# AlcoholDetectieV2.net
KiCad netlist of a schematic drawn in Altium Designer
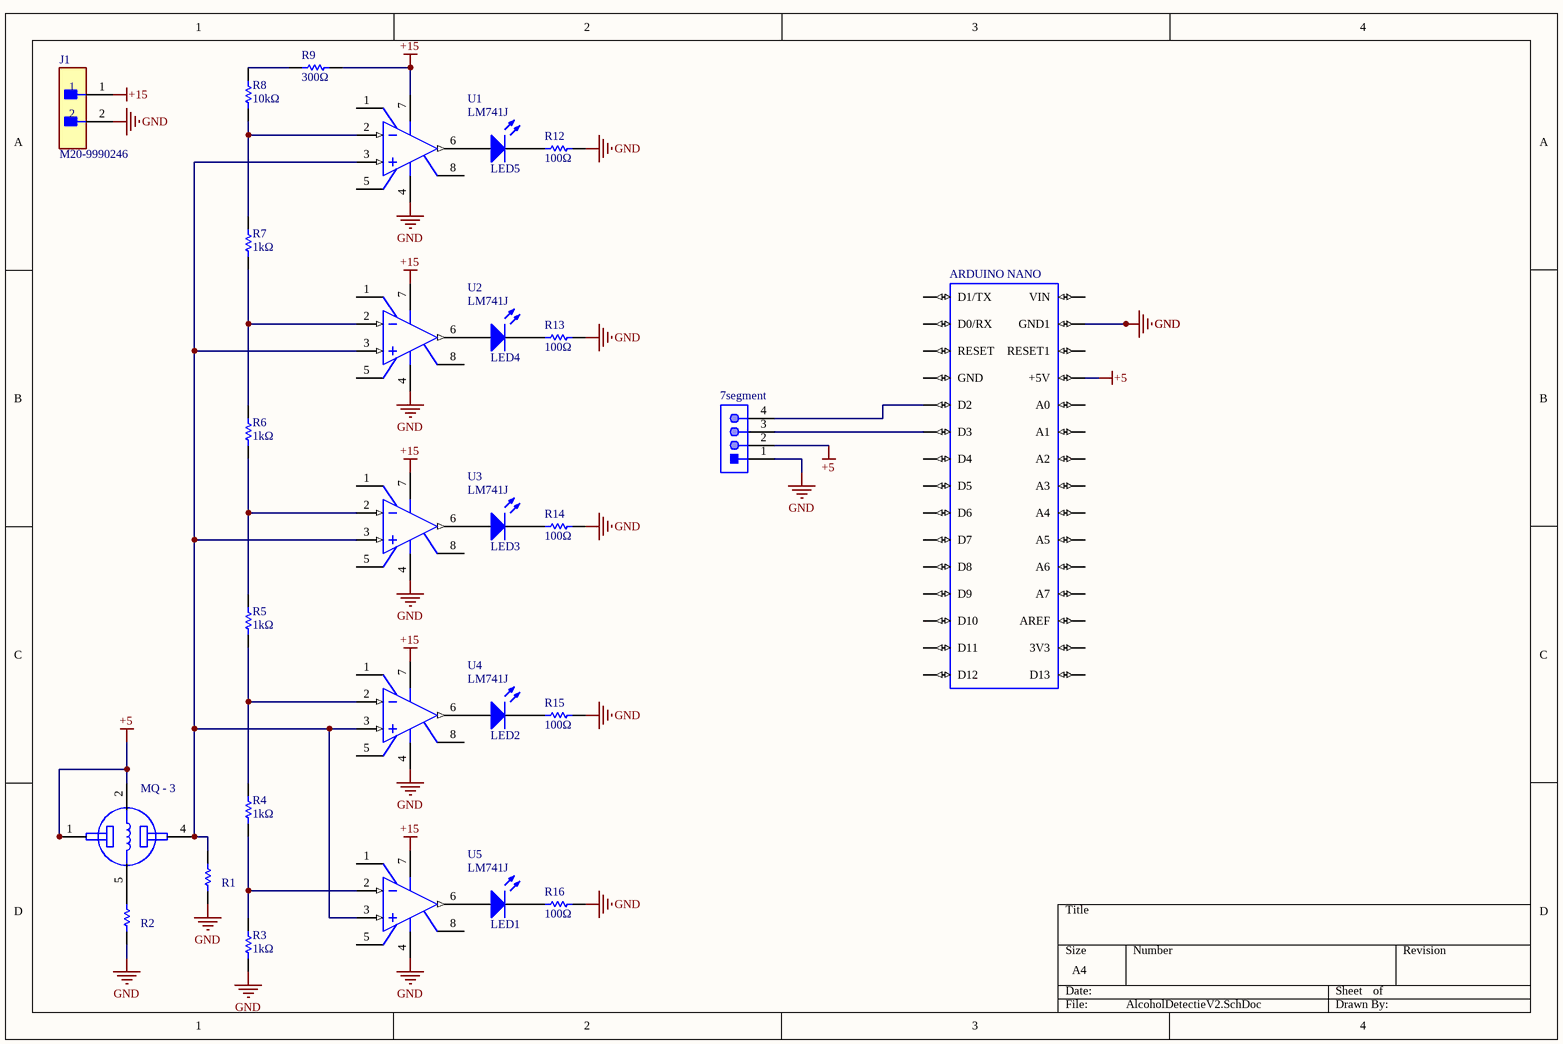
[diagram p0: AlcoholDetectieV2.SchDoc]

(export (version "E")
  (design (tool "Eeschema 10.0.6"))
  (components
    (comp (ref "7segment")
      (value "61300411121")
      (footprint "61300411121")
      (description "THT Vertical Pin Header WR-PHD, Pitch 2.54 mm, Single Row, 4 pins")
      (fields (field (name "MANUFACTURER") "Wurth Elektronik") (field (name "PUBLISHER") "WurthElektronik"))
      (libsource (lib "Altium Content Vault") (part "WE-CN-1P-M-R4"))
    )
    (comp (ref "ARDUINO NANO")
      (value "ARDUINONANO")
      (footprint "PDIP-32")
      (description "Arduino; 20MHz; 3.3Ã·5VDC; Flash: 32kB; SRAM: 2kB; ATMEGA328,FT232R")
      (fields (field (name "MF") "Arduino"))
      (libsource (lib "ARDUINONANO") (part "ARDUINONANO"))
    )
    (comp (ref "GROEN")
      (value "LED1")
      (footprint "LED-1")
      (description "Typical RED GaAs LED")
      (fields (field (name "PUBLISHER") "Altium Limited"))
      (libsource (lib "Miscellaneous Devices") (part "LED1"))
    )
    (comp (ref "J1")
      (value "M20-9990246")
      (footprint "FP-M20-9990246-MFG")
      (description "CONN HEADER VERT 2POS 2.54MM")
      (fields
        (field (name "OCTOPART") "https://octopart.com/m20-9990246-harwin-2590635")
        (field (name "MANUFACTURER") "Harwin")
      )
      (libsource (lib "Altium Content Vault") (part "3bc925449376181038e59eaffc5286c"))
    )
    (comp (ref "MQ - 3")
      (value "SEN-08880")
      (footprint "XDCR_SEN-08880")
      (description "Alcohol _C2H6O_ Sensor 0 V ~ 3.3 V")
      (fields (field (name "MF") "SparkFun Electronics"))
      (libsource (lib "SEN-08880") (part "SEN-08880"))
    )
    (comp (ref "ORANJE_1")
      (value "LED2")
      (footprint "LED-1")
      (description "Typical RED GaAs LED")
      (fields (field (name "PUBLISHER") "Altium Limited"))
      (libsource (lib "Miscellaneous Devices") (part "LED1"))
    )
    (comp (ref "ORANJE_2")
      (value "LED3")
      (footprint "LED-1")
      (description "Typical RED GaAs LED")
      (fields (field (name "PUBLISHER") "Altium Limited"))
      (libsource (lib "Miscellaneous Devices") (part "LED1"))
    )
    (comp (ref "R1")
      (value "1k Ω")
      (footprint "RESC2013X50X30LL20T20")
      (fields (field (name "MANUFACTURER") "Vishay Dale") (field (name "PART NUMBER") "CRCW08050000Z0EA"))
      (libsource (lib "Altium Content Vault") (part "RES"))
    )
    (comp (ref "R2")
      (value "5,1 Ω")
      (footprint "RESC2013X50X30LL20T20")
      (fields (field (name "MANUFACTURER") "Vishay Dale") (field (name "PART NUMBER") "CRCW08050000Z0EA"))
      (libsource (lib "Altium Content Vault") (part "RES"))
    )
    (comp (ref "R3")
      (value "1kΩ")
      (footprint "RESC2013X50X30LL20T20")
      (fields (field (name "MANUFACTURER") "Vishay Dale") (field (name "PART NUMBER") "CRCW08050000Z0EA"))
      (libsource (lib "Altium Content Vault") (part "RES"))
    )
    (comp (ref "R4")
      (value "1kΩ")
      (footprint "RESC2013X50X30LL20T20")
      (fields (field (name "MANUFACTURER") "Vishay Dale") (field (name "PART NUMBER") "CRCW08050000Z0EA"))
      (libsource (lib "Altium Content Vault") (part "RES"))
    )
    (comp (ref "R5")
      (value "1kΩ")
      (footprint "RESC2013X50X30LL20T20")
      (fields (field (name "MANUFACTURER") "Vishay Dale") (field (name "PART NUMBER") "CRCW08050000Z0EA"))
      (libsource (lib "Altium Content Vault") (part "RES"))
    )
    (comp (ref "R6")
      (value "1kΩ")
      (footprint "RESC2013X50X30LL20T20")
      (fields (field (name "MANUFACTURER") "Vishay Dale") (field (name "PART NUMBER") "CRCW08050000Z0EA"))
      (libsource (lib "Altium Content Vault") (part "RES"))
    )
    (comp (ref "R7")
      (value "1kΩ")
      (footprint "RESC2013X50X30LL20T20")
      (fields (field (name "MANUFACTURER") "Vishay Dale") (field (name "PART NUMBER") "CRCW08050000Z0EA"))
      (libsource (lib "Altium Content Vault") (part "RES"))
    )
    (comp (ref "R8")
      (value "10kΩ")
      (footprint "RESC2013X50X30LL20T20")
      (fields (field (name "MANUFACTURER") "Vishay Dale") (field (name "PART NUMBER") "CRCW08050000Z0EA"))
      (libsource (lib "Altium Content Vault") (part "RES"))
    )
    (comp (ref "R9")
      (value "300Ω")
      (footprint "RESC2013X50X30LL20T20")
      (fields (field (name "MANUFACTURER") "Vishay Dale") (field (name "PART NUMBER") "CRCW08050000Z0EA"))
      (libsource (lib "Altium Content Vault") (part "RES"))
    )
    (comp (ref "R12")
      (value "100Ω")
      (footprint "RESC2013X50X30LL20T20")
      (fields (field (name "MANUFACTURER") "Vishay Dale") (field (name "PART NUMBER") "CRCW08050000Z0EA"))
      (libsource (lib "Altium Content Vault") (part "RES"))
    )
    (comp (ref "R13")
      (value "100Ω")
      (footprint "RESC2013X50X30LL20T20")
      (fields (field (name "MANUFACTURER") "Vishay Dale") (field (name "PART NUMBER") "CRCW08050000Z0EA"))
      (libsource (lib "Altium Content Vault") (part "RES"))
    )
    (comp (ref "R14")
      (value "100Ω")
      (footprint "RESC2013X50X30LL20T20")
      (fields (field (name "MANUFACTURER") "Vishay Dale") (field (name "PART NUMBER") "CRCW08050000Z0EA"))
      (libsource (lib "Altium Content Vault") (part "RES"))
    )
    (comp (ref "R15")
      (value "100Ω")
      (footprint "RESC2013X50X30LL20T20")
      (fields (field (name "MANUFACTURER") "Vishay Dale") (field (name "PART NUMBER") "CRCW08050000Z0EA"))
      (libsource (lib "Altium Content Vault") (part "RES"))
    )
    (comp (ref "R16")
      (value "100Ω")
      (footprint "RESC2013X50X30LL20T20")
      (fields (field (name "MANUFACTURER") "Vishay Dale") (field (name "PART NUMBER") "CRCW08050000Z0EA"))
      (libsource (lib "Altium Content Vault") (part "RES"))
    )
    (comp (ref "ROOD_1")
      (value "LED4")
      (footprint "LED-1")
      (description "Typical RED GaAs LED")
      (fields (field (name "PUBLISHER") "Altium Limited"))
      (libsource (lib "Miscellaneous Devices") (part "LED1"))
    )
    (comp (ref "ROOD_2")
      (value "LED5")
      (footprint "LED-1")
      (description "Typical RED GaAs LED")
      (fields (field (name "PUBLISHER") "Altium Limited"))
      (libsource (lib "Miscellaneous Devices") (part "LED1"))
    )
    (comp (ref "U1")
      (value "LM741J")
      (footprint "NAB0008A")
      (description "Operational Amplifier, 8-pin CerDIP")
      (fields (field (name "MANUFACTURER") "Texas Instruments"))
      (libsource (lib "Altium Content Vault") (part "AMP-OPA-LM741-8"))
    )
    (comp (ref "U2")
      (value "LM741J")
      (footprint "NAB0008A")
      (description "Operational Amplifier, 8-pin CerDIP")
      (fields (field (name "MANUFACTURER") "Texas Instruments"))
      (libsource (lib "Altium Content Vault") (part "AMP-OPA-LM741-8"))
    )
    (comp (ref "U3")
      (value "LM741J")
      (footprint "NAB0008A")
      (description "Operational Amplifier, 8-pin CerDIP")
      (fields (field (name "MANUFACTURER") "Texas Instruments"))
      (libsource (lib "Altium Content Vault") (part "AMP-OPA-LM741-8"))
    )
    (comp (ref "U4")
      (value "LM741J")
      (footprint "NAB0008A")
      (description "Operational Amplifier, 8-pin CerDIP")
      (fields (field (name "MANUFACTURER") "Texas Instruments"))
      (libsource (lib "Altium Content Vault") (part "AMP-OPA-LM741-8"))
    )
    (comp (ref "U5")
      (value "LM741J")
      (footprint "NAB0008A")
      (description "Operational Amplifier, 8-pin CerDIP")
      (fields (field (name "MANUFACTURER") "Texas Instruments"))
      (libsource (lib "Altium Content Vault") (part "AMP-OPA-LM741-8"))
    )
  )
  (nets
    (net (code "1") (name "+5") (class "Default")
      (node (ref "7segment") (pin "2") (pinfunction "2_2") (pintype "passive"))
      (node (ref "ARDUINO NANO") (pin "+5V") (pinfunction "+5V_+5V") (pintype "bidirectional"))
      (node (ref "MQ - 3") (pin "1") (pinfunction "A_1") (pintype "passive"))
      (node (ref "MQ - 3") (pin "2") (pinfunction "H1_2") (pintype "passive"))
      (node (ref "MQ - 3") (pin "3") (pinfunction "A_3") (pintype "passive"))
    )
    (net (code "2") (name "+15") (class "Default")
      (node (ref "J1") (pin "1") (pinfunction "1_1") (pintype "passive"))
      (node (ref "R9") (pin "1") (pinfunction "1_1") (pintype "passive"))
      (node (ref "U1") (pin "7") (pinfunction "V+_7") (pintype "power_in"))
      (node (ref "U2") (pin "7") (pinfunction "V+_7") (pintype "power_in"))
      (node (ref "U3") (pin "7") (pinfunction "V+_7") (pintype "power_in"))
      (node (ref "U4") (pin "7") (pinfunction "V+_7") (pintype "power_in"))
      (node (ref "U5") (pin "7") (pinfunction "V+_7") (pintype "power_in"))
    )
    (net (code "3") (name "GND") (class "Default")
      (node (ref "7segment") (pin "1") (pinfunction "1_1") (pintype "passive"))
      (node (ref "ARDUINO NANO") (pin "GND1") (pinfunction "GND1_GND1") (pintype "bidirectional"))
      (node (ref "J1") (pin "2") (pinfunction "2_2") (pintype "passive"))
      (node (ref "R1") (pin "1") (pinfunction "1_1") (pintype "passive"))
      (node (ref "R12") (pin "1") (pinfunction "1_1") (pintype "passive"))
      (node (ref "R13") (pin "1") (pinfunction "1_1") (pintype "passive"))
      (node (ref "R14") (pin "1") (pinfunction "1_1") (pintype "passive"))
      (node (ref "R15") (pin "1") (pinfunction "1_1") (pintype "passive"))
      (node (ref "R16") (pin "1") (pinfunction "1_1") (pintype "passive"))
      (node (ref "R2") (pin "1") (pinfunction "1_1") (pintype "passive"))
      (node (ref "R3") (pin "1") (pinfunction "1_1") (pintype "passive"))
      (node (ref "U1") (pin "4") (pinfunction "V-_4") (pintype "power_in"))
      (node (ref "U2") (pin "4") (pinfunction "V-_4") (pintype "power_in"))
      (node (ref "U3") (pin "4") (pinfunction "V-_4") (pintype "power_in"))
      (node (ref "U4") (pin "4") (pinfunction "V-_4") (pintype "power_in"))
      (node (ref "U5") (pin "4") (pinfunction "V-_4") (pintype "power_in"))
    )
    (net (code "4") (name "Net-(7segment-Pad3)") (class "Default")
      (node (ref "7segment") (pin "3") (pinfunction "3_3") (pintype "passive"))
      (node (ref "ARDUINO NANO") (pin "D3") (pinfunction "D3_D3") (pintype "bidirectional"))
    )
    (net (code "5") (name "Net-(7segment-Pad4)") (class "Default")
      (node (ref "7segment") (pin "4") (pinfunction "4_4") (pintype "passive"))
      (node (ref "ARDUINO NANO") (pin "D2") (pinfunction "D2_D2") (pintype "bidirectional"))
    )
    (net (code "6") (name "Net-(GROEN-A)") (class "Default")
      (node (ref "GROEN") (pin "1") (pinfunction "A_1") (pintype "passive"))
      (node (ref "U5") (pin "6") (pinfunction "OUT_6") (pintype "output"))
    )
    (net (code "7") (name "Net-(GROEN-K)") (class "Default")
      (node (ref "GROEN") (pin "2") (pinfunction "K_2") (pintype "passive"))
      (node (ref "R16") (pin "2") (pinfunction "2_2") (pintype "passive"))
    )
    (net (code "8") (name "Net-(MQ - 3-H2)") (class "Default")
      (node (ref "MQ - 3") (pin "5") (pinfunction "H2_5") (pintype "passive"))
      (node (ref "R2") (pin "2") (pinfunction "2_2") (pintype "passive"))
    )
    (net (code "9") (name "Net-(ORANJE_1-A)") (class "Default")
      (node (ref "ORANJE_1") (pin "1") (pinfunction "A_1") (pintype "passive"))
      (node (ref "U4") (pin "6") (pinfunction "OUT_6") (pintype "output"))
    )
    (net (code "10") (name "Net-(ORANJE_1-K)") (class "Default")
      (node (ref "ORANJE_1") (pin "2") (pinfunction "K_2") (pintype "passive"))
      (node (ref "R15") (pin "2") (pinfunction "2_2") (pintype "passive"))
    )
    (net (code "11") (name "Net-(ORANJE_2-A)") (class "Default")
      (node (ref "ORANJE_2") (pin "1") (pinfunction "A_1") (pintype "passive"))
      (node (ref "U3") (pin "6") (pinfunction "OUT_6") (pintype "output"))
    )
    (net (code "12") (name "Net-(ORANJE_2-K)") (class "Default")
      (node (ref "ORANJE_2") (pin "2") (pinfunction "K_2") (pintype "passive"))
      (node (ref "R14") (pin "2") (pinfunction "2_2") (pintype "passive"))
    )
    (net (code "13") (name "Net-(R8-Pad2)") (class "Default")
      (node (ref "R8") (pin "2") (pinfunction "2_2") (pintype "passive"))
      (node (ref "R9") (pin "2") (pinfunction "2_2") (pintype "passive"))
    )
    (net (code "14") (name "Net-(ROOD_1-A)") (class "Default")
      (node (ref "ROOD_1") (pin "1") (pinfunction "A_1") (pintype "passive"))
      (node (ref "U2") (pin "6") (pinfunction "OUT_6") (pintype "output"))
    )
    (net (code "15") (name "Net-(ROOD_1-K)") (class "Default")
      (node (ref "R13") (pin "2") (pinfunction "2_2") (pintype "passive"))
      (node (ref "ROOD_1") (pin "2") (pinfunction "K_2") (pintype "passive"))
    )
    (net (code "16") (name "Net-(ROOD_2-A)") (class "Default")
      (node (ref "ROOD_2") (pin "1") (pinfunction "A_1") (pintype "passive"))
      (node (ref "U1") (pin "6") (pinfunction "OUT_6") (pintype "output"))
    )
    (net (code "17") (name "Net-(ROOD_2-K)") (class "Default")
      (node (ref "R12") (pin "2") (pinfunction "2_2") (pintype "passive"))
      (node (ref "ROOD_2") (pin "2") (pinfunction "K_2") (pintype "passive"))
    )
    (net (code "18") (name "Net-(U1-IN+)") (class "Default")
      (node (ref "MQ - 3") (pin "4") (pinfunction "B_4") (pintype "passive"))
      (node (ref "MQ - 3") (pin "6") (pinfunction "B_6") (pintype "passive"))
      (node (ref "R1") (pin "2") (pinfunction "2_2") (pintype "passive"))
      (node (ref "U1") (pin "3") (pinfunction "IN+_3") (pintype "input"))
      (node (ref "U2") (pin "3") (pinfunction "IN+_3") (pintype "input"))
      (node (ref "U3") (pin "3") (pinfunction "IN+_3") (pintype "input"))
      (node (ref "U4") (pin "3") (pinfunction "IN+_3") (pintype "input"))
      (node (ref "U5") (pin "3") (pinfunction "IN+_3") (pintype "input"))
    )
    (net (code "19") (name "Net-(U1-IN-)") (class "Default")
      (node (ref "R7") (pin "2") (pinfunction "2_2") (pintype "passive"))
      (node (ref "R8") (pin "1") (pinfunction "1_1") (pintype "passive"))
      (node (ref "U1") (pin "2") (pinfunction "IN-_2") (pintype "input"))
    )
    (net (code "20") (name "Net-(U2-IN-)") (class "Default")
      (node (ref "R6") (pin "2") (pinfunction "2_2") (pintype "passive"))
      (node (ref "R7") (pin "1") (pinfunction "1_1") (pintype "passive"))
      (node (ref "U2") (pin "2") (pinfunction "IN-_2") (pintype "input"))
    )
    (net (code "21") (name "Net-(U3-IN-)") (class "Default")
      (node (ref "R5") (pin "2") (pinfunction "2_2") (pintype "passive"))
      (node (ref "R6") (pin "1") (pinfunction "1_1") (pintype "passive"))
      (node (ref "U3") (pin "2") (pinfunction "IN-_2") (pintype "input"))
    )
    (net (code "22") (name "Net-(U4-IN-)") (class "Default")
      (node (ref "R4") (pin "2") (pinfunction "2_2") (pintype "passive"))
      (node (ref "R5") (pin "1") (pinfunction "1_1") (pintype "passive"))
      (node (ref "U4") (pin "2") (pinfunction "IN-_2") (pintype "input"))
    )
    (net (code "23") (name "Net-(U5-IN-)") (class "Default")
      (node (ref "R3") (pin "2") (pinfunction "2_2") (pintype "passive"))
      (node (ref "R4") (pin "1") (pinfunction "1_1") (pintype "passive"))
      (node (ref "U5") (pin "2") (pinfunction "IN-_2") (pintype "input"))
    )
    (net (code "24") (name "unconnected-(ARDUINO NANO-Pad3V3)") (class "Default")
      (node (ref "ARDUINO NANO") (pin "3V3") (pinfunction "3V3_3V3") (pintype "bidirectional"))
    )
    (net (code "25") (name "unconnected-(ARDUINO NANO-PadA0)") (class "Default")
      (node (ref "ARDUINO NANO") (pin "A0") (pinfunction "A0_A0") (pintype "bidirectional"))
    )
    (net (code "26") (name "unconnected-(ARDUINO NANO-PadA1)") (class "Default")
      (node (ref "ARDUINO NANO") (pin "A1") (pinfunction "A1_A1") (pintype "bidirectional"))
    )
    (net (code "27") (name "unconnected-(ARDUINO NANO-PadA2)") (class "Default")
      (node (ref "ARDUINO NANO") (pin "A2") (pinfunction "A2_A2") (pintype "bidirectional"))
    )
    (net (code "28") (name "unconnected-(ARDUINO NANO-PadA3)") (class "Default")
      (node (ref "ARDUINO NANO") (pin "A3") (pinfunction "A3_A3") (pintype "bidirectional"))
    )
    (net (code "29") (name "unconnected-(ARDUINO NANO-PadA4)") (class "Default")
      (node (ref "ARDUINO NANO") (pin "A4") (pinfunction "A4_A4") (pintype "bidirectional"))
    )
    (net (code "30") (name "unconnected-(ARDUINO NANO-PadA5)") (class "Default")
      (node (ref "ARDUINO NANO") (pin "A5") (pinfunction "A5_A5") (pintype "bidirectional"))
    )
    (net (code "31") (name "unconnected-(ARDUINO NANO-PadA6)") (class "Default")
      (node (ref "ARDUINO NANO") (pin "A6") (pinfunction "A6_A6") (pintype "bidirectional"))
    )
    (net (code "32") (name "unconnected-(ARDUINO NANO-PadA7)") (class "Default")
      (node (ref "ARDUINO NANO") (pin "A7") (pinfunction "A7_A7") (pintype "bidirectional"))
    )
    (net (code "33") (name "unconnected-(ARDUINO NANO-PadAREF)") (class "Default")
      (node (ref "ARDUINO NANO") (pin "AREF") (pinfunction "AREF_AREF") (pintype "bidirectional"))
    )
    (net (code "34") (name "unconnected-(ARDUINO NANO-PadD0{slash}RX)") (class "Default")
      (node (ref "ARDUINO NANO") (pin "D0/RX") (pinfunction "D0/RX_D0/RX") (pintype "bidirectional"))
    )
    (net (code "35") (name "unconnected-(ARDUINO NANO-PadD1{slash}TX)") (class "Default")
      (node (ref "ARDUINO NANO") (pin "D1/TX") (pinfunction "D1/TX_D1/TX") (pintype "bidirectional"))
    )
    (net (code "36") (name "unconnected-(ARDUINO NANO-PadD4)") (class "Default")
      (node (ref "ARDUINO NANO") (pin "D4") (pinfunction "D4_D4") (pintype "bidirectional"))
    )
    (net (code "37") (name "unconnected-(ARDUINO NANO-PadD5)") (class "Default")
      (node (ref "ARDUINO NANO") (pin "D5") (pinfunction "D5_D5") (pintype "bidirectional"))
    )
    (net (code "38") (name "unconnected-(ARDUINO NANO-PadD6)") (class "Default")
      (node (ref "ARDUINO NANO") (pin "D6") (pinfunction "D6_D6") (pintype "bidirectional"))
    )
    (net (code "39") (name "unconnected-(ARDUINO NANO-PadD7)") (class "Default")
      (node (ref "ARDUINO NANO") (pin "D7") (pinfunction "D7_D7") (pintype "bidirectional"))
    )
    (net (code "40") (name "unconnected-(ARDUINO NANO-PadD8)") (class "Default")
      (node (ref "ARDUINO NANO") (pin "D8") (pinfunction "D8_D8") (pintype "bidirectional"))
    )
    (net (code "41") (name "unconnected-(ARDUINO NANO-PadD9)") (class "Default")
      (node (ref "ARDUINO NANO") (pin "D9") (pinfunction "D9_D9") (pintype "bidirectional"))
    )
    (net (code "42") (name "unconnected-(ARDUINO NANO-PadD10)") (class "Default")
      (node (ref "ARDUINO NANO") (pin "D10") (pinfunction "D10_D10") (pintype "bidirectional"))
    )
    (net (code "43") (name "unconnected-(ARDUINO NANO-PadD11)") (class "Default")
      (node (ref "ARDUINO NANO") (pin "D11") (pinfunction "D11_D11") (pintype "bidirectional"))
    )
    (net (code "44") (name "unconnected-(ARDUINO NANO-PadD12)") (class "Default")
      (node (ref "ARDUINO NANO") (pin "D12") (pinfunction "D12_D12") (pintype "bidirectional"))
    )
    (net (code "45") (name "unconnected-(ARDUINO NANO-PadD13)") (class "Default")
      (node (ref "ARDUINO NANO") (pin "D13") (pinfunction "D13_D13") (pintype "bidirectional"))
    )
    (net (code "46") (name "unconnected-(ARDUINO NANO-PadGND)") (class "Default")
      (node (ref "ARDUINO NANO") (pin "GND") (pinfunction "GND_GND") (pintype "bidirectional"))
    )
    (net (code "47") (name "unconnected-(ARDUINO NANO-PadRESET)") (class "Default")
      (node (ref "ARDUINO NANO") (pin "RESET") (pinfunction "RESET_RESET") (pintype "bidirectional"))
    )
    (net (code "48") (name "unconnected-(ARDUINO NANO-PadRESET1)") (class "Default")
      (node (ref "ARDUINO NANO") (pin "RESET1") (pinfunction "RESET1_RESET1") (pintype "bidirectional"))
    )
    (net (code "49") (name "unconnected-(ARDUINO NANO-PadVIN)") (class "Default")
      (node (ref "ARDUINO NANO") (pin "VIN") (pinfunction "VIN_VIN") (pintype "bidirectional"))
    )
    (net (code "50") (name "unconnected-(U1-NC-Pad8)") (class "Default")
      (node (ref "U1") (pin "8") (pinfunction "NC_8") (pintype "passive"))
    )
    (net (code "51") (name "unconnected-(U1-OFS_NULL-Pad1)") (class "Default")
      (node (ref "U1") (pin "1") (pinfunction "OFS_NULL_1") (pintype "passive"))
    )
    (net (code "52") (name "unconnected-(U1-OFS_NULL-Pad5)") (class "Default")
      (node (ref "U1") (pin "5") (pinfunction "OFS_NULL_5") (pintype "passive"))
    )
    (net (code "53") (name "unconnected-(U2-NC-Pad8)") (class "Default")
      (node (ref "U2") (pin "8") (pinfunction "NC_8") (pintype "passive"))
    )
    (net (code "54") (name "unconnected-(U2-OFS_NULL-Pad1)") (class "Default")
      (node (ref "U2") (pin "1") (pinfunction "OFS_NULL_1") (pintype "passive"))
    )
    (net (code "55") (name "unconnected-(U2-OFS_NULL-Pad5)") (class "Default")
      (node (ref "U2") (pin "5") (pinfunction "OFS_NULL_5") (pintype "passive"))
    )
    (net (code "56") (name "unconnected-(U3-NC-Pad8)") (class "Default")
      (node (ref "U3") (pin "8") (pinfunction "NC_8") (pintype "passive"))
    )
    (net (code "57") (name "unconnected-(U3-OFS_NULL-Pad1)") (class "Default")
      (node (ref "U3") (pin "1") (pinfunction "OFS_NULL_1") (pintype "passive"))
    )
    (net (code "58") (name "unconnected-(U3-OFS_NULL-Pad5)") (class "Default")
      (node (ref "U3") (pin "5") (pinfunction "OFS_NULL_5") (pintype "passive"))
    )
    (net (code "59") (name "unconnected-(U4-NC-Pad8)") (class "Default")
      (node (ref "U4") (pin "8") (pinfunction "NC_8") (pintype "passive"))
    )
    (net (code "60") (name "unconnected-(U4-OFS_NULL-Pad1)") (class "Default")
      (node (ref "U4") (pin "1") (pinfunction "OFS_NULL_1") (pintype "passive"))
    )
    (net (code "61") (name "unconnected-(U4-OFS_NULL-Pad5)") (class "Default")
      (node (ref "U4") (pin "5") (pinfunction "OFS_NULL_5") (pintype "passive"))
    )
    (net (code "62") (name "unconnected-(U5-NC-Pad8)") (class "Default")
      (node (ref "U5") (pin "8") (pinfunction "NC_8") (pintype "passive"))
    )
    (net (code "63") (name "unconnected-(U5-OFS_NULL-Pad1)") (class "Default")
      (node (ref "U5") (pin "1") (pinfunction "OFS_NULL_1") (pintype "passive"))
    )
    (net (code "64") (name "unconnected-(U5-OFS_NULL-Pad5)") (class "Default")
      (node (ref "U5") (pin "5") (pinfunction "OFS_NULL_5") (pintype "passive"))
    )
  )
)
